# Macropad.net
KiCad netlist of a schematic drawn in EAGLE
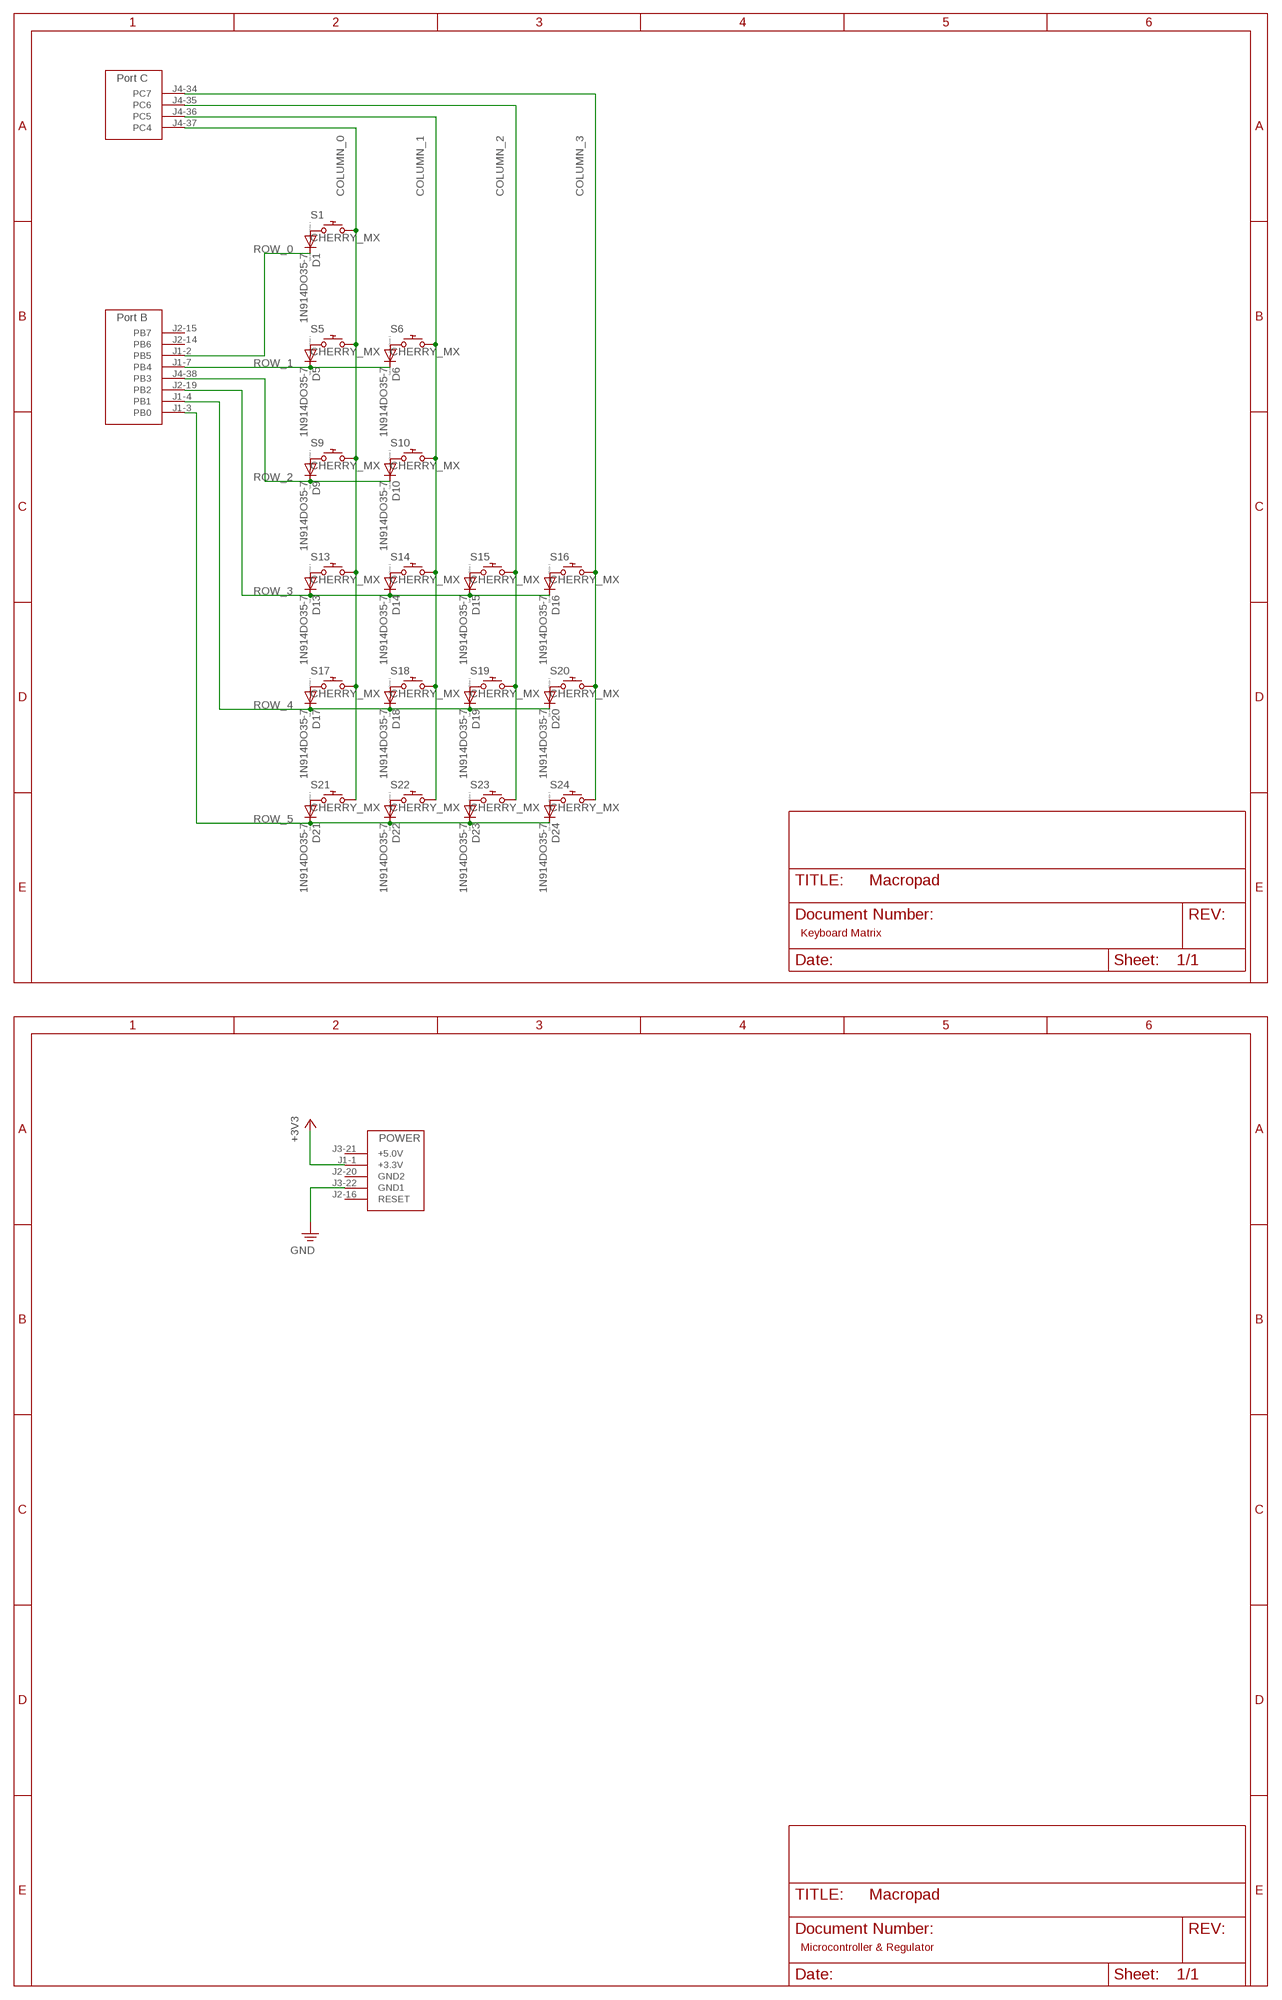
[diagram p0: schematic, sheet 1, part 1 of 2]
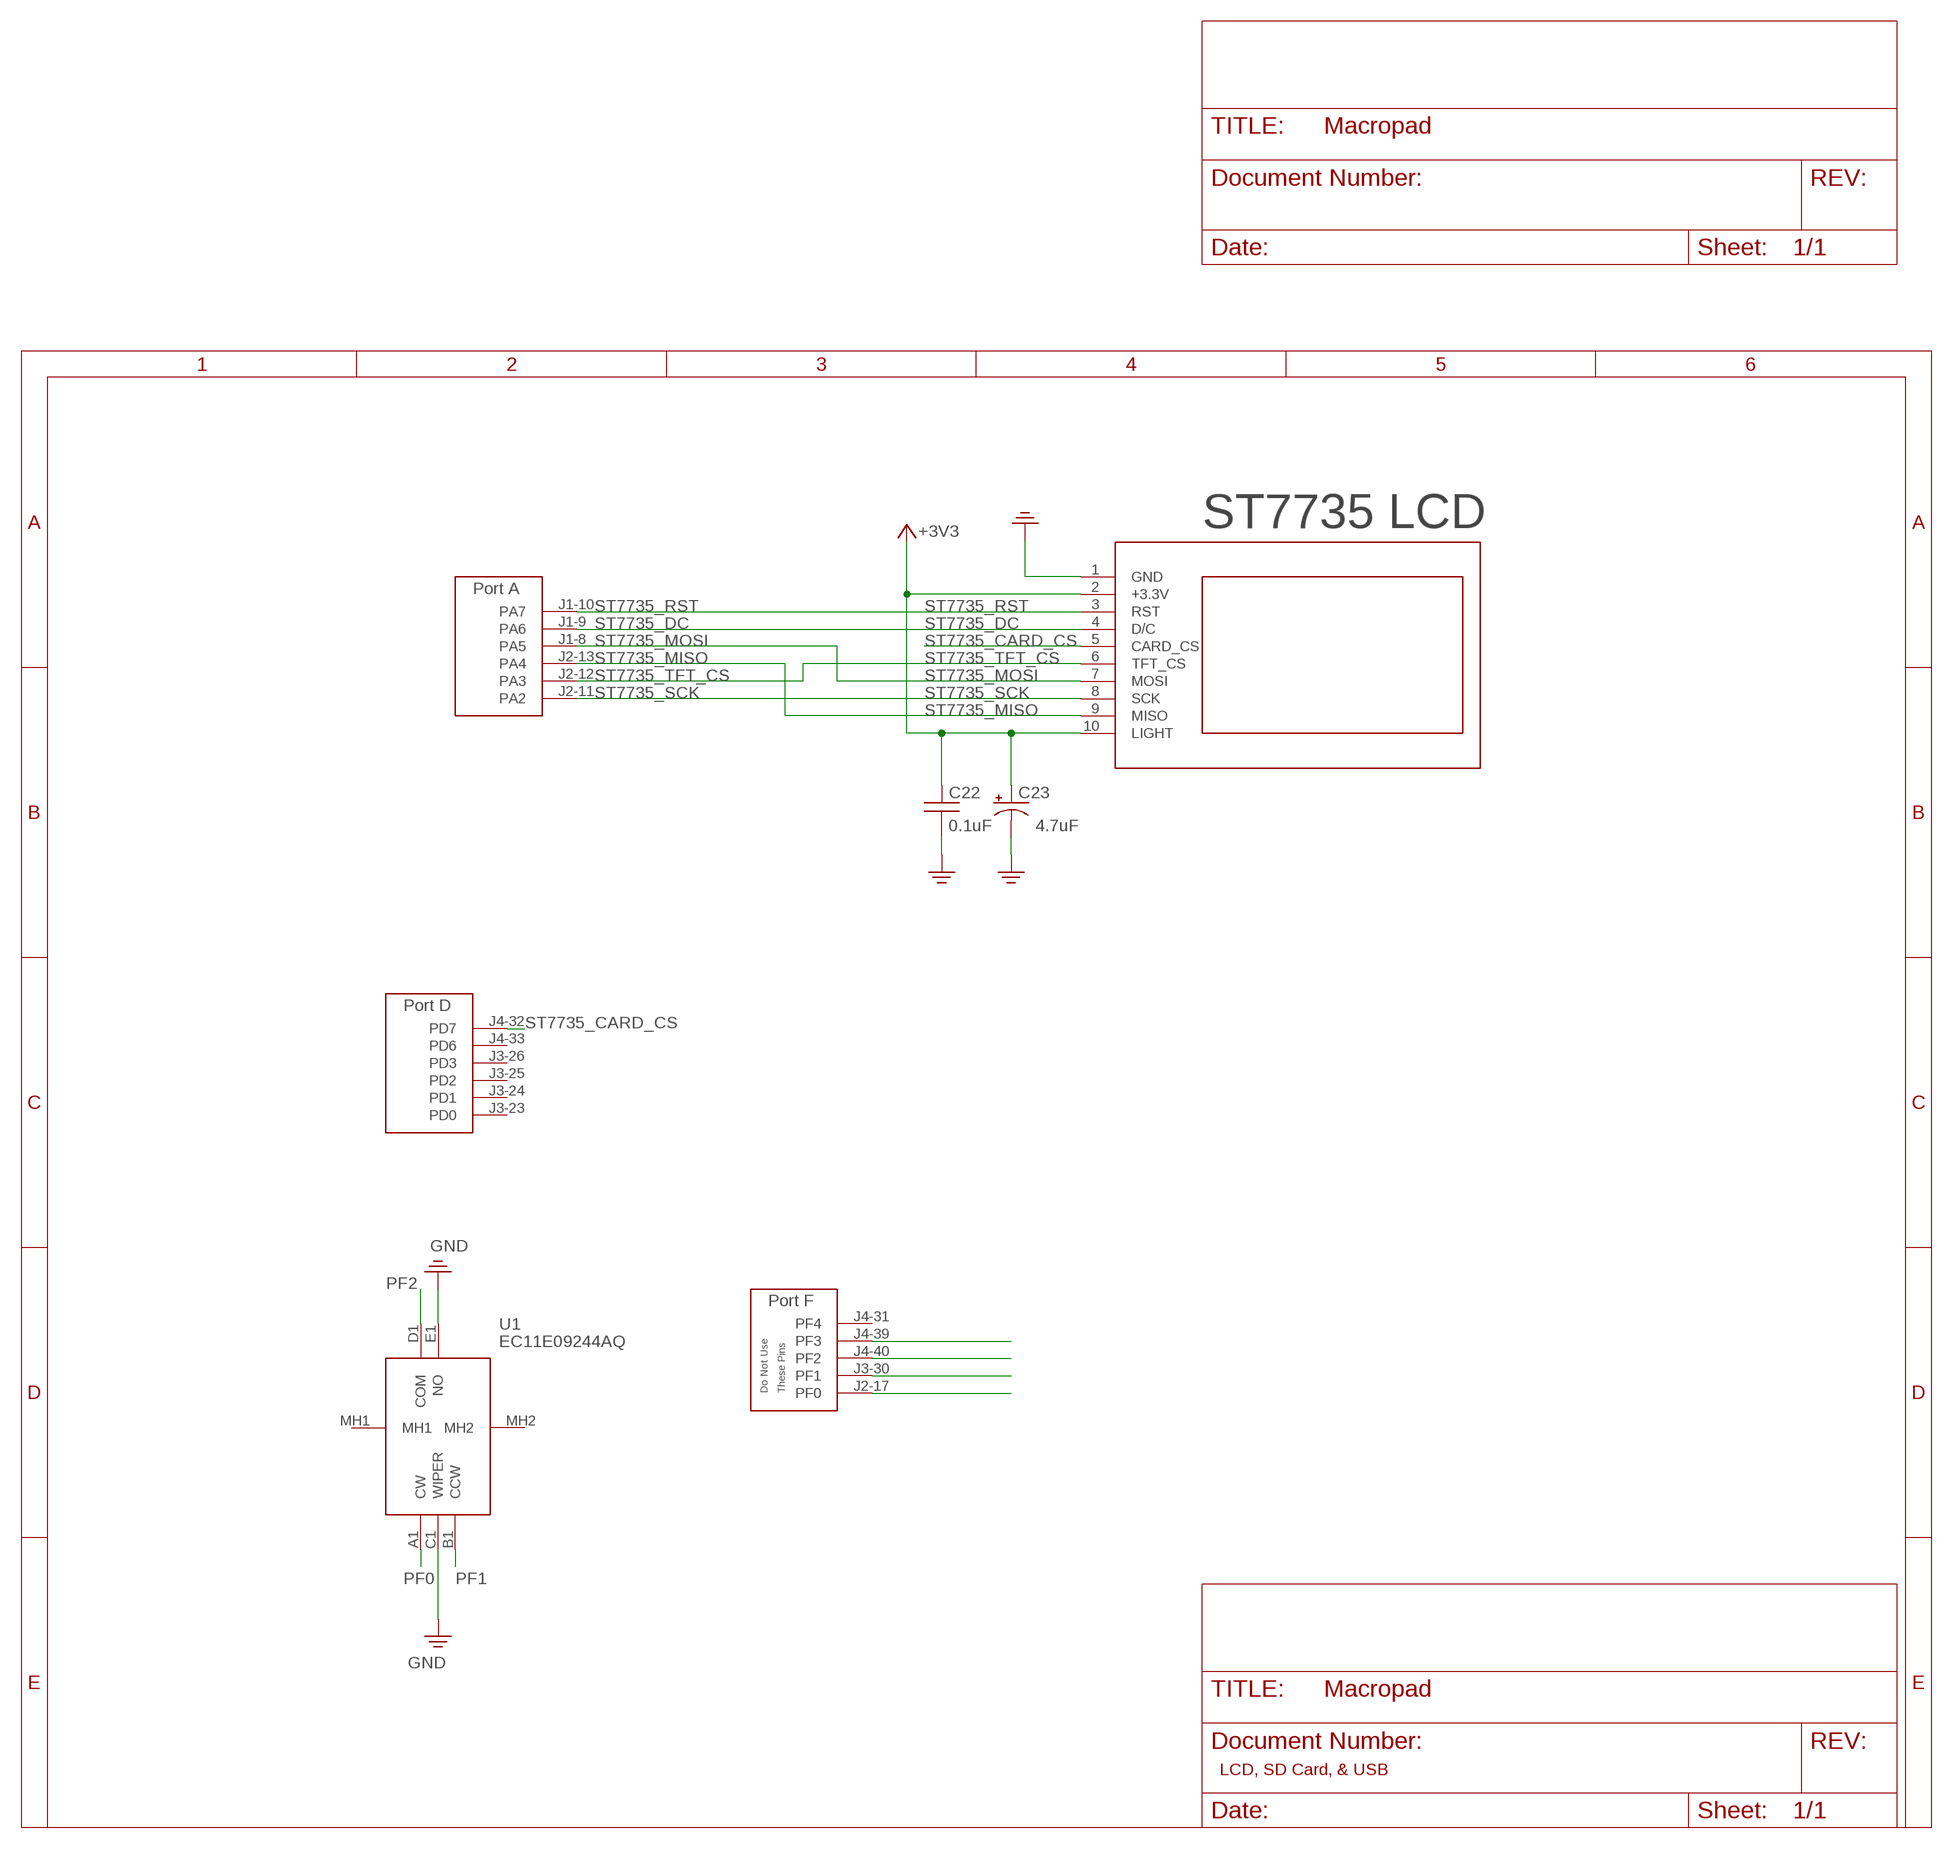
[diagram p1: schematic, sheet 1, part 2 of 2]

(export (version "E")
  (design (tool "Eeschema 10.0.6"))
  (components
    (comp (ref "C22")
      (value "0.1uF")
      (footprint "eagle-import:CAP200MIL")
      (libsource (lib "eagle-import") (part "CAPACITOR050-024X044"))
    )
    (comp (ref "C23")
      (value "4.7uF")
      (footprint "eagle-import:CAP200MILPOLARIZED")
      (libsource (lib "eagle-import") (part "CAPACITOR_POLARIZEDE5-6"))
    )
    (comp (ref "D1")
      (value "1N914DO35-7")
      (footprint "eagle-import:DO35-7")
      (libsource (lib "eagle-import") (part "1N914DO35-7"))
    )
    (comp (ref "D5")
      (value "1N914DO35-7")
      (footprint "eagle-import:DO35-7")
      (libsource (lib "eagle-import") (part "1N914DO35-7"))
    )
    (comp (ref "D6")
      (value "1N914DO35-7")
      (footprint "eagle-import:DO35-7")
      (libsource (lib "eagle-import") (part "1N914DO35-7"))
    )
    (comp (ref "D9")
      (value "1N914DO35-7")
      (footprint "eagle-import:DO35-7")
      (libsource (lib "eagle-import") (part "1N914DO35-7"))
    )
    (comp (ref "D10")
      (value "1N914DO35-7")
      (footprint "eagle-import:DO35-7")
      (libsource (lib "eagle-import") (part "1N914DO35-7"))
    )
    (comp (ref "D13")
      (value "1N914DO35-7")
      (footprint "eagle-import:DO35-7")
      (libsource (lib "eagle-import") (part "1N914DO35-7"))
    )
    (comp (ref "D14")
      (value "1N914DO35-7")
      (footprint "eagle-import:DO35-7")
      (libsource (lib "eagle-import") (part "1N914DO35-7"))
    )
    (comp (ref "D15")
      (value "1N914DO35-7")
      (footprint "eagle-import:DO35-7")
      (libsource (lib "eagle-import") (part "1N914DO35-7"))
    )
    (comp (ref "D16")
      (value "1N914DO35-7")
      (footprint "eagle-import:DO35-7")
      (libsource (lib "eagle-import") (part "1N914DO35-7"))
    )
    (comp (ref "D17")
      (value "1N914DO35-7")
      (footprint "eagle-import:DO35-7")
      (libsource (lib "eagle-import") (part "1N914DO35-7"))
    )
    (comp (ref "D18")
      (value "1N914DO35-7")
      (footprint "eagle-import:DO35-7")
      (libsource (lib "eagle-import") (part "1N914DO35-7"))
    )
    (comp (ref "D19")
      (value "1N914DO35-7")
      (footprint "eagle-import:DO35-7")
      (libsource (lib "eagle-import") (part "1N914DO35-7"))
    )
    (comp (ref "D20")
      (value "1N914DO35-7")
      (footprint "eagle-import:DO35-7")
      (libsource (lib "eagle-import") (part "1N914DO35-7"))
    )
    (comp (ref "D21")
      (value "1N914DO35-7")
      (footprint "eagle-import:DO35-7")
      (libsource (lib "eagle-import") (part "1N914DO35-7"))
    )
    (comp (ref "D22")
      (value "1N914DO35-7")
      (footprint "eagle-import:DO35-7")
      (libsource (lib "eagle-import") (part "1N914DO35-7"))
    )
    (comp (ref "D23")
      (value "1N914DO35-7")
      (footprint "eagle-import:DO35-7")
      (libsource (lib "eagle-import") (part "1N914DO35-7"))
    )
    (comp (ref "D24")
      (value "1N914DO35-7")
      (footprint "eagle-import:DO35-7")
      (libsource (lib "eagle-import") (part "1N914DO35-7"))
    )
    (comp (ref "S1")
      (value "CHERRY_MX")
      (footprint "eagle-import:CHERRY_MX")
      (libsource (lib "eagle-import") (part "CHERRY_MX"))
    )
    (comp (ref "S5")
      (value "CHERRY_MX")
      (footprint "eagle-import:CHERRY_MX")
      (libsource (lib "eagle-import") (part "CHERRY_MX"))
    )
    (comp (ref "S6")
      (value "CHERRY_MX")
      (footprint "eagle-import:CHERRY_MX")
      (libsource (lib "eagle-import") (part "CHERRY_MX"))
    )
    (comp (ref "S9")
      (value "CHERRY_MX")
      (footprint "eagle-import:CHERRY_MX")
      (libsource (lib "eagle-import") (part "CHERRY_MX"))
    )
    (comp (ref "S10")
      (value "CHERRY_MX")
      (footprint "eagle-import:CHERRY_MX")
      (libsource (lib "eagle-import") (part "CHERRY_MX"))
    )
    (comp (ref "S13")
      (value "CHERRY_MX")
      (footprint "eagle-import:CHERRY_MX")
      (libsource (lib "eagle-import") (part "CHERRY_MX"))
    )
    (comp (ref "S14")
      (value "CHERRY_MX")
      (footprint "eagle-import:CHERRY_MX")
      (libsource (lib "eagle-import") (part "CHERRY_MX"))
    )
    (comp (ref "S15")
      (value "CHERRY_MX")
      (footprint "eagle-import:CHERRY_MX")
      (libsource (lib "eagle-import") (part "CHERRY_MX"))
    )
    (comp (ref "S16")
      (value "CHERRY_MX")
      (footprint "eagle-import:CHERRY_MX")
      (libsource (lib "eagle-import") (part "CHERRY_MX"))
    )
    (comp (ref "S17")
      (value "CHERRY_MX")
      (footprint "eagle-import:CHERRY_MX")
      (libsource (lib "eagle-import") (part "CHERRY_MX"))
    )
    (comp (ref "S18")
      (value "CHERRY_MX")
      (footprint "eagle-import:CHERRY_MX")
      (libsource (lib "eagle-import") (part "CHERRY_MX"))
    )
    (comp (ref "S19")
      (value "CHERRY_MX")
      (footprint "eagle-import:CHERRY_MX")
      (libsource (lib "eagle-import") (part "CHERRY_MX"))
    )
    (comp (ref "S20")
      (value "CHERRY_MX")
      (footprint "eagle-import:CHERRY_MX")
      (libsource (lib "eagle-import") (part "CHERRY_MX"))
    )
    (comp (ref "S21")
      (value "CHERRY_MX")
      (footprint "eagle-import:CHERRY_MX")
      (libsource (lib "eagle-import") (part "CHERRY_MX"))
    )
    (comp (ref "S22")
      (value "CHERRY_MX")
      (footprint "eagle-import:CHERRY_MX")
      (libsource (lib "eagle-import") (part "CHERRY_MX"))
    )
    (comp (ref "S23")
      (value "CHERRY_MX")
      (footprint "eagle-import:CHERRY_MX")
      (libsource (lib "eagle-import") (part "CHERRY_MX"))
    )
    (comp (ref "S24")
      (value "CHERRY_MX")
      (footprint "eagle-import:CHERRY_MX")
      (libsource (lib "eagle-import") (part "CHERRY_MX"))
    )
    (comp (ref "U$2")
      (value "TM4C_BP")
      (footprint "eagle-import:TM4C_BOOSTER_PACK")
      (libsource (lib "eagle-import") (part "TM4C_BP"))
    )
    (comp (ref "U$6")
      (value "ST7735")
      (footprint "eagle-import:ST7735")
      (libsource (lib "eagle-import") (part "ST7735"))
    )
    (comp (ref "U1")
      (value "EC11E09244AQ")
      (footprint "eagle-import:EC11E09244AQ")
      (fields (field (name "MOUSER_PART_NUMBER") "688-EC11E09244AQ"))
      (libsource (lib "eagle-import") (part "EC11E09244AQ"))
    )
  )
  (nets
    (net (code "1") (name "+3V3") (class "Default")
      (node (ref "C22") (pin "1") (pinfunction "1_1") (pintype "passive"))
      (node (ref "C23") (pin "+") (pinfunction "+_+") (pintype "passive"))
      (node (ref "U$2") (pin "J1-1") (pinfunction "+3.3V_J1-1") (pintype "bidirectional"))
      (node (ref "U$6") (pin "10") (pinfunction "LIGHT_10") (pintype "bidirectional"))
      (node (ref "U$6") (pin "2") (pinfunction "+3.3V_2") (pintype "bidirectional"))
    )
    (net (code "2") (name "/COLUMN_0") (class "Default")
      (node (ref "S1") (pin "S2") (pinfunction "2_S2") (pintype "passive"))
      (node (ref "S13") (pin "S2") (pinfunction "2_S2") (pintype "passive"))
      (node (ref "S17") (pin "S2") (pinfunction "2_S2") (pintype "passive"))
      (node (ref "S21") (pin "S2") (pinfunction "2_S2") (pintype "passive"))
      (node (ref "S5") (pin "S2") (pinfunction "2_S2") (pintype "passive"))
      (node (ref "S9") (pin "S2") (pinfunction "2_S2") (pintype "passive"))
      (node (ref "U$2") (pin "J4-37") (pinfunction "PC4_J4-37") (pintype "bidirectional"))
    )
    (net (code "3") (name "/COLUMN_1") (class "Default")
      (node (ref "S10") (pin "S2") (pinfunction "2_S2") (pintype "passive"))
      (node (ref "S14") (pin "S2") (pinfunction "2_S2") (pintype "passive"))
      (node (ref "S18") (pin "S2") (pinfunction "2_S2") (pintype "passive"))
      (node (ref "S22") (pin "S2") (pinfunction "2_S2") (pintype "passive"))
      (node (ref "S6") (pin "S2") (pinfunction "2_S2") (pintype "passive"))
      (node (ref "U$2") (pin "J4-36") (pinfunction "PC5_J4-36") (pintype "bidirectional"))
    )
    (net (code "4") (name "/COLUMN_2") (class "Default")
      (node (ref "S15") (pin "S2") (pinfunction "2_S2") (pintype "passive"))
      (node (ref "S19") (pin "S2") (pinfunction "2_S2") (pintype "passive"))
      (node (ref "S23") (pin "S2") (pinfunction "2_S2") (pintype "passive"))
      (node (ref "U$2") (pin "J4-35") (pinfunction "PC6_J4-35") (pintype "bidirectional"))
    )
    (net (code "5") (name "/COLUMN_3") (class "Default")
      (node (ref "S16") (pin "S2") (pinfunction "2_S2") (pintype "passive"))
      (node (ref "S20") (pin "S2") (pinfunction "2_S2") (pintype "passive"))
      (node (ref "S24") (pin "S2") (pinfunction "2_S2") (pintype "passive"))
      (node (ref "U$2") (pin "J4-34") (pinfunction "PC7_J4-34") (pintype "bidirectional"))
    )
    (net (code "6") (name "/PF0") (class "Default")
      (node (ref "U$2") (pin "J2-17") (pinfunction "PF0_J2-17") (pintype "bidirectional"))
      (node (ref "U1") (pin "A1") (pinfunction "CW_A1") (pintype "bidirectional"))
    )
    (net (code "7") (name "/PF1") (class "Default")
      (node (ref "U$2") (pin "J3-30") (pinfunction "PF1_J3-30") (pintype "bidirectional"))
      (node (ref "U1") (pin "B1") (pinfunction "CCW_B1") (pintype "bidirectional"))
    )
    (net (code "8") (name "/PF2") (class "Default")
      (node (ref "U$2") (pin "J4-40") (pinfunction "PF2_J4-40") (pintype "bidirectional"))
      (node (ref "U1") (pin "D1") (pinfunction "COM_D1") (pintype "bidirectional"))
    )
    (net (code "9") (name "/ROW_0") (class "Default")
      (node (ref "D1") (pin "C") (pinfunction "C_C") (pintype "passive"))
      (node (ref "U$2") (pin "J1-2") (pinfunction "PB5_J1-2") (pintype "bidirectional"))
    )
    (net (code "10") (name "/ROW_1") (class "Default")
      (node (ref "D5") (pin "C") (pinfunction "C_C") (pintype "passive"))
      (node (ref "D6") (pin "C") (pinfunction "C_C") (pintype "passive"))
      (node (ref "U$2") (pin "J1-7") (pinfunction "PB4_J1-7") (pintype "bidirectional"))
    )
    (net (code "11") (name "/ROW_2") (class "Default")
      (node (ref "D10") (pin "C") (pinfunction "C_C") (pintype "passive"))
      (node (ref "D9") (pin "C") (pinfunction "C_C") (pintype "passive"))
      (node (ref "U$2") (pin "J4-38") (pinfunction "PB3_J4-38") (pintype "bidirectional"))
    )
    (net (code "12") (name "/ROW_3") (class "Default")
      (node (ref "D13") (pin "C") (pinfunction "C_C") (pintype "passive"))
      (node (ref "D14") (pin "C") (pinfunction "C_C") (pintype "passive"))
      (node (ref "D15") (pin "C") (pinfunction "C_C") (pintype "passive"))
      (node (ref "D16") (pin "C") (pinfunction "C_C") (pintype "passive"))
      (node (ref "U$2") (pin "J2-19") (pinfunction "PB2_J2-19") (pintype "bidirectional"))
    )
    (net (code "13") (name "/ROW_4") (class "Default")
      (node (ref "D17") (pin "C") (pinfunction "C_C") (pintype "passive"))
      (node (ref "D18") (pin "C") (pinfunction "C_C") (pintype "passive"))
      (node (ref "D19") (pin "C") (pinfunction "C_C") (pintype "passive"))
      (node (ref "D20") (pin "C") (pinfunction "C_C") (pintype "passive"))
      (node (ref "U$2") (pin "J1-4") (pinfunction "PB1_J1-4") (pintype "bidirectional"))
    )
    (net (code "14") (name "/ROW_5") (class "Default")
      (node (ref "D21") (pin "C") (pinfunction "C_C") (pintype "passive"))
      (node (ref "D22") (pin "C") (pinfunction "C_C") (pintype "passive"))
      (node (ref "D23") (pin "C") (pinfunction "C_C") (pintype "passive"))
      (node (ref "D24") (pin "C") (pinfunction "C_C") (pintype "passive"))
      (node (ref "U$2") (pin "J1-3") (pinfunction "PB0_J1-3") (pintype "bidirectional"))
    )
    (net (code "15") (name "/ST7735_CARD_CS") (class "Default")
      (node (ref "U$2") (pin "J4-32") (pinfunction "PD7_J4-32") (pintype "bidirectional"))
      (node (ref "U$6") (pin "5") (pinfunction "CARD_CS_5") (pintype "bidirectional"))
    )
    (net (code "16") (name "/ST7735_DC") (class "Default")
      (node (ref "U$2") (pin "J1-9") (pinfunction "PA6_J1-9") (pintype "bidirectional"))
      (node (ref "U$6") (pin "4") (pinfunction "D/C_4") (pintype "bidirectional"))
    )
    (net (code "17") (name "/ST7735_MISO") (class "Default")
      (node (ref "U$2") (pin "J2-13") (pinfunction "PA4_J2-13") (pintype "bidirectional"))
      (node (ref "U$6") (pin "9") (pinfunction "MISO_9") (pintype "bidirectional"))
    )
    (net (code "18") (name "/ST7735_MOSI") (class "Default")
      (node (ref "U$2") (pin "J1-8") (pinfunction "PA5_J1-8") (pintype "bidirectional"))
      (node (ref "U$6") (pin "7") (pinfunction "MOSI_7") (pintype "bidirectional"))
    )
    (net (code "19") (name "/ST7735_RST") (class "Default")
      (node (ref "U$2") (pin "J1-10") (pinfunction "PA7_J1-10") (pintype "bidirectional"))
      (node (ref "U$6") (pin "3") (pinfunction "RST_3") (pintype "bidirectional"))
    )
    (net (code "20") (name "/ST7735_SCK") (class "Default")
      (node (ref "U$2") (pin "J2-11") (pinfunction "PA2_J2-11") (pintype "bidirectional"))
      (node (ref "U$6") (pin "8") (pinfunction "SCK_8") (pintype "bidirectional"))
    )
    (net (code "21") (name "/ST7735_TFT_CS") (class "Default")
      (node (ref "U$2") (pin "J2-12") (pinfunction "PA3_J2-12") (pintype "bidirectional"))
      (node (ref "U$6") (pin "6") (pinfunction "TFT_CS_6") (pintype "bidirectional"))
    )
    (net (code "22") (name "GND") (class "Default")
      (node (ref "C22") (pin "2") (pinfunction "2_2") (pintype "passive"))
      (node (ref "C23") (pin "-") (pinfunction "-_-") (pintype "passive"))
      (node (ref "U$2") (pin "J3-22") (pinfunction "GND1_J3-22") (pintype "bidirectional"))
      (node (ref "U$6") (pin "1") (pinfunction "GND_1") (pintype "bidirectional"))
      (node (ref "U1") (pin "C1") (pinfunction "WIPER_C1") (pintype "bidirectional"))
      (node (ref "U1") (pin "E1") (pinfunction "NO_E1") (pintype "bidirectional"))
    )
    (net (code "23") (name "Net-(S1-1)") (class "Default")
      (node (ref "D1") (pin "A") (pinfunction "A_A") (pintype "passive"))
      (node (ref "S1") (pin "S1") (pinfunction "1_S1") (pintype "passive"))
    )
    (net (code "24") (name "Net-(S5-1)") (class "Default")
      (node (ref "D5") (pin "A") (pinfunction "A_A") (pintype "passive"))
      (node (ref "S5") (pin "S1") (pinfunction "1_S1") (pintype "passive"))
    )
    (net (code "25") (name "Net-(S6-1)") (class "Default")
      (node (ref "D6") (pin "A") (pinfunction "A_A") (pintype "passive"))
      (node (ref "S6") (pin "S1") (pinfunction "1_S1") (pintype "passive"))
    )
    (net (code "26") (name "Net-(S9-1)") (class "Default")
      (node (ref "D9") (pin "A") (pinfunction "A_A") (pintype "passive"))
      (node (ref "S9") (pin "S1") (pinfunction "1_S1") (pintype "passive"))
    )
    (net (code "27") (name "Net-(S10-1)") (class "Default")
      (node (ref "D10") (pin "A") (pinfunction "A_A") (pintype "passive"))
      (node (ref "S10") (pin "S1") (pinfunction "1_S1") (pintype "passive"))
    )
    (net (code "28") (name "Net-(S13-1)") (class "Default")
      (node (ref "D13") (pin "A") (pinfunction "A_A") (pintype "passive"))
      (node (ref "S13") (pin "S1") (pinfunction "1_S1") (pintype "passive"))
    )
    (net (code "29") (name "Net-(S14-1)") (class "Default")
      (node (ref "D14") (pin "A") (pinfunction "A_A") (pintype "passive"))
      (node (ref "S14") (pin "S1") (pinfunction "1_S1") (pintype "passive"))
    )
    (net (code "30") (name "Net-(S15-1)") (class "Default")
      (node (ref "D15") (pin "A") (pinfunction "A_A") (pintype "passive"))
      (node (ref "S15") (pin "S1") (pinfunction "1_S1") (pintype "passive"))
    )
    (net (code "31") (name "Net-(S16-1)") (class "Default")
      (node (ref "D16") (pin "A") (pinfunction "A_A") (pintype "passive"))
      (node (ref "S16") (pin "S1") (pinfunction "1_S1") (pintype "passive"))
    )
    (net (code "32") (name "Net-(S17-1)") (class "Default")
      (node (ref "D17") (pin "A") (pinfunction "A_A") (pintype "passive"))
      (node (ref "S17") (pin "S1") (pinfunction "1_S1") (pintype "passive"))
    )
    (net (code "33") (name "Net-(S18-1)") (class "Default")
      (node (ref "D18") (pin "A") (pinfunction "A_A") (pintype "passive"))
      (node (ref "S18") (pin "S1") (pinfunction "1_S1") (pintype "passive"))
    )
    (net (code "34") (name "Net-(S19-1)") (class "Default")
      (node (ref "D19") (pin "A") (pinfunction "A_A") (pintype "passive"))
      (node (ref "S19") (pin "S1") (pinfunction "1_S1") (pintype "passive"))
    )
    (net (code "35") (name "Net-(S20-1)") (class "Default")
      (node (ref "D20") (pin "A") (pinfunction "A_A") (pintype "passive"))
      (node (ref "S20") (pin "S1") (pinfunction "1_S1") (pintype "passive"))
    )
    (net (code "36") (name "Net-(S21-1)") (class "Default")
      (node (ref "D21") (pin "A") (pinfunction "A_A") (pintype "passive"))
      (node (ref "S21") (pin "S1") (pinfunction "1_S1") (pintype "passive"))
    )
    (net (code "37") (name "Net-(S22-1)") (class "Default")
      (node (ref "D22") (pin "A") (pinfunction "A_A") (pintype "passive"))
      (node (ref "S22") (pin "S1") (pinfunction "1_S1") (pintype "passive"))
    )
    (net (code "38") (name "Net-(S23-1)") (class "Default")
      (node (ref "D23") (pin "A") (pinfunction "A_A") (pintype "passive"))
      (node (ref "S23") (pin "S1") (pinfunction "1_S1") (pintype "passive"))
    )
    (net (code "39") (name "Net-(S24-1)") (class "Default")
      (node (ref "D24") (pin "A") (pinfunction "A_A") (pintype "passive"))
      (node (ref "S24") (pin "S1") (pinfunction "1_S1") (pintype "passive"))
    )
    (net (code "40") (name "unconnected-(U$2B-PB6-PadJ2-14)") (class "Default")
      (node (ref "U$2") (pin "J2-14") (pinfunction "PB6_J2-14") (pintype "bidirectional"))
    )
    (net (code "41") (name "unconnected-(U$2B-PB7-PadJ2-15)") (class "Default")
      (node (ref "U$2") (pin "J2-15") (pinfunction "PB7_J2-15") (pintype "bidirectional"))
    )
    (net (code "42") (name "unconnected-(U$2D-PD0-PadJ3-23)") (class "Default")
      (node (ref "U$2") (pin "J3-23") (pinfunction "PD0_J3-23") (pintype "bidirectional"))
    )
    (net (code "43") (name "unconnected-(U$2D-PD1-PadJ3-24)") (class "Default")
      (node (ref "U$2") (pin "J3-24") (pinfunction "PD1_J3-24") (pintype "bidirectional"))
    )
    (net (code "44") (name "unconnected-(U$2D-PD2-PadJ3-25)") (class "Default")
      (node (ref "U$2") (pin "J3-25") (pinfunction "PD2_J3-25") (pintype "bidirectional"))
    )
    (net (code "45") (name "unconnected-(U$2D-PD3-PadJ3-26)") (class "Default")
      (node (ref "U$2") (pin "J3-26") (pinfunction "PD3_J3-26") (pintype "bidirectional"))
    )
    (net (code "46") (name "unconnected-(U$2D-PD6-PadJ4-33)") (class "Default")
      (node (ref "U$2") (pin "J4-33") (pinfunction "PD6_J4-33") (pintype "bidirectional"))
    )
    (net (code "47") (name "unconnected-(U$2F-PF3-PadJ4-39)") (class "Default")
      (node (ref "U$2") (pin "J4-39") (pinfunction "PF3_J4-39") (pintype "bidirectional"))
    )
    (net (code "48") (name "unconnected-(U$2F-PF4-PadJ4-31)") (class "Default")
      (node (ref "U$2") (pin "J4-31") (pinfunction "PF4_J4-31") (pintype "bidirectional"))
    )
    (net (code "49") (name "unconnected-(U$2G-+5.0V-PadJ3-21)") (class "Default")
      (node (ref "U$2") (pin "J3-21") (pinfunction "+5.0V_J3-21") (pintype "bidirectional"))
    )
    (net (code "50") (name "unconnected-(U$2G-GND2-PadJ2-20)") (class "Default")
      (node (ref "U$2") (pin "J2-20") (pinfunction "GND2_J2-20") (pintype "bidirectional"))
    )
    (net (code "51") (name "unconnected-(U$2G-RESET-PadJ2-16)") (class "Default")
      (node (ref "U$2") (pin "J2-16") (pinfunction "RESET_J2-16") (pintype "bidirectional"))
    )
    (net (code "52") (name "unconnected-(U1-PadMH1)") (class "Default")
      (node (ref "U1") (pin "MH1") (pinfunction "MH1_MH1") (pintype "bidirectional"))
    )
    (net (code "53") (name "unconnected-(U1-PadMH2)") (class "Default")
      (node (ref "U1") (pin "MH2") (pinfunction "MH2_MH2") (pintype "bidirectional"))
    )
  )
)
